# try2.net
KiCad netlist of a schematic drawn in EAGLE
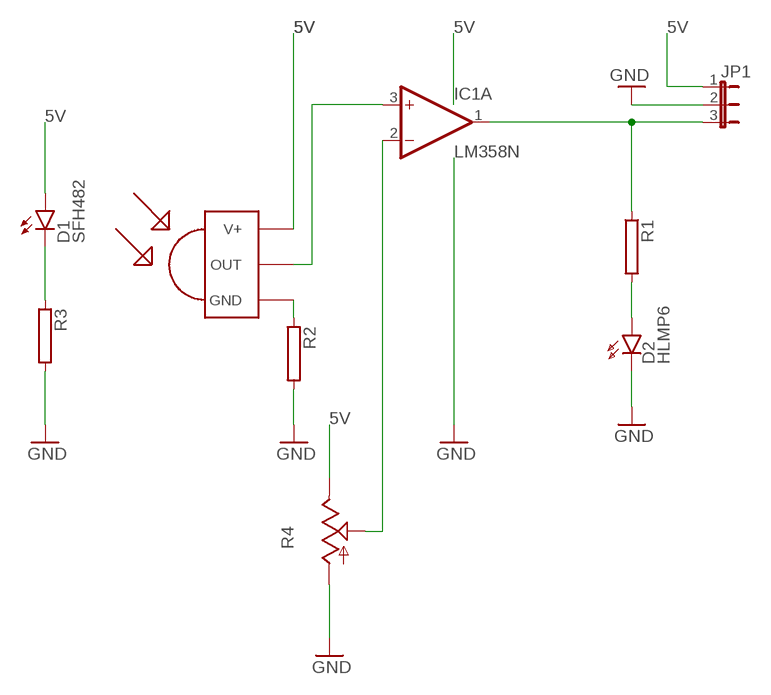
[diagram p0: schematic, sheet 1]

(export (version "E")
  (design (tool "Eeschema 10.0.6"))
  (components
    (comp (ref "D1")
      (value "SFH482")
      (footprint "eagle-import:SFH482")
      (libsource (lib "eagle-import") (part "SFH482"))
    )
    (comp (ref "D2")
      (value "HLMP6")
      (footprint "eagle-import:HLMP6")
      (fields (field (name "MF") "AGILENT TECHNOLOGIES") (field (name "MPN") "HLMP-6500"))
      (libsource (lib "eagle-import") (part "HLMP6"))
    )
    (comp (ref "IC1")
      (value "LM358N")
      (footprint "eagle-import:DIL08")
      (libsource (lib "eagle-import") (part "LM358N"))
    )
    (comp (ref "JP1")
      (value "JP2E")
      (footprint "eagle-import:JP2")
      (libsource (lib "eagle-import") (part "JP2E"))
    )
    (comp (ref "R1")
      (value "RAC01")
      (footprint "eagle-import:AC01")
      (libsource (lib "eagle-import") (part "RAC01"))
    )
    (comp (ref "R2")
      (value "RAC01")
      (footprint "eagle-import:AC01")
      (libsource (lib "eagle-import") (part "RAC01"))
    )
    (comp (ref "R3")
      (value "RAC01")
      (footprint "eagle-import:AC01")
      (libsource (lib "eagle-import") (part "RAC01"))
    )
    (comp (ref "R4")
      (value "TRIM_US-CA9H")
      (footprint "eagle-import:CA9H")
      (libsource (lib "eagle-import") (part "TRIM_US-CA9H"))
    )
    (comp (ref "TSOP1")
      (value "TSOP1730")
      (footprint "eagle-import:TSOP17XX")
      (libsource (lib "eagle-import") (part "TSOP1730"))
    )
  )
  (nets
    (net (code "1") (name "/5V") (class "Default")
      (node (ref "D1") (pin "A") (pinfunction "A_A") (pintype "passive"))
      (node (ref "R4") (pin "E") (pinfunction "E_E") (pintype "passive"))
      (node (ref "TSOP1") (pin "V+") (pinfunction "V+_V+") (pintype "bidirectional"))
    )
    (net (code "2") (name "GND") (class "Default")
      (node (ref "D2") (pin "K") (pinfunction "K_K") (pintype "passive"))
      (node (ref "JP1") (pin "2") (pinfunction "2_2") (pintype "passive"))
      (node (ref "R2") (pin "2") (pinfunction "2_2") (pintype "passive"))
      (node (ref "R3") (pin "2") (pinfunction "2_2") (pintype "passive"))
      (node (ref "R4") (pin "A") (pinfunction "A_A") (pintype "passive"))
    )
    (net (code "3") (name "Net-(D1-C)") (class "Default")
      (node (ref "D1") (pin "K") (pinfunction "C_K") (pintype "passive"))
      (node (ref "R3") (pin "1") (pinfunction "1_1") (pintype "passive"))
    )
    (net (code "4") (name "Net-(D2-PadA)") (class "Default")
      (node (ref "D2") (pin "A") (pinfunction "A_A") (pintype "passive"))
      (node (ref "R1") (pin "2") (pinfunction "2_2") (pintype "passive"))
    )
    (net (code "5") (name "Net-(IC1A-+IN)") (class "Default")
      (node (ref "IC1") (pin "3") (pinfunction "+IN_3") (pintype "input"))
      (node (ref "TSOP1") (pin "OUT") (pinfunction "OUT_OUT") (pintype "bidirectional"))
    )
    (net (code "6") (name "Net-(IC1A--IN)") (class "Default")
      (node (ref "IC1") (pin "2") (pinfunction "-IN_2") (pintype "input"))
      (node (ref "R4") (pin "S") (pinfunction "S_S") (pintype "passive"))
    )
    (net (code "7") (name "Net-(IC1A-OUT)") (class "Default")
      (node (ref "IC1") (pin "1") (pinfunction "OUT_1") (pintype "output"))
      (node (ref "JP1") (pin "3") (pinfunction "3_3") (pintype "passive"))
      (node (ref "R1") (pin "1") (pinfunction "1_1") (pintype "passive"))
    )
    (net (code "8") (name "Net-(R2-Pad1)") (class "Default")
      (node (ref "R2") (pin "1") (pinfunction "1_1") (pintype "passive"))
      (node (ref "TSOP1") (pin "GND") (pinfunction "GND_GND") (pintype "bidirectional"))
    )
    (net (code "9") (name "unconnected-(JP1-Pad1)") (class "Default")
      (node (ref "JP1") (pin "1") (pinfunction "1_1") (pintype "passive"))
    )
  )
)
